# Spartan6-IO23.net
KiCad netlist of a schematic drawn in Altium Designer
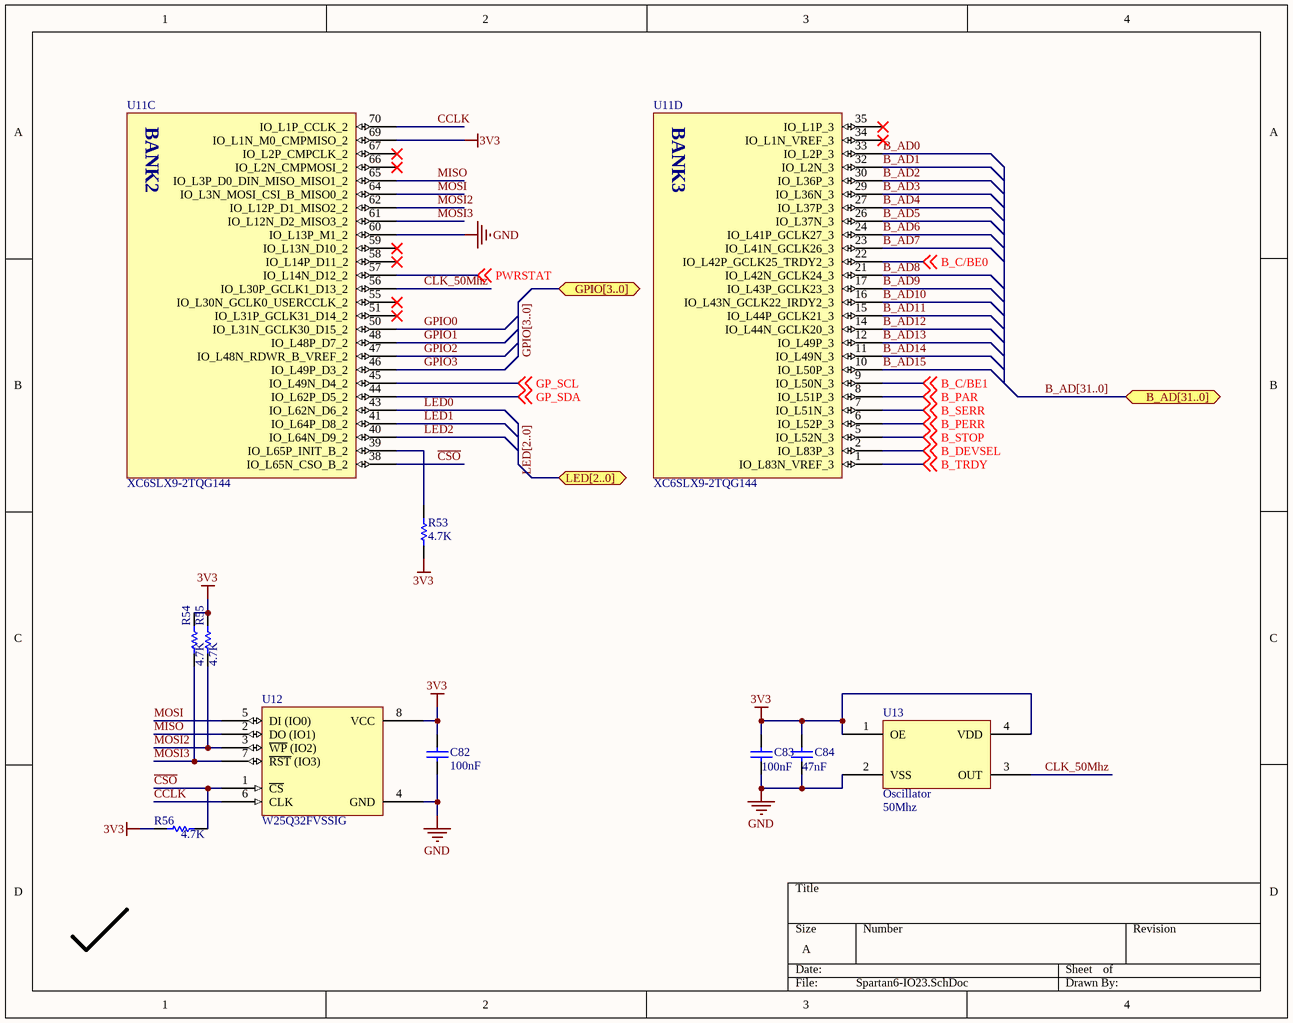
[diagram p0: Spartan6-IO23.SchDoc]

(export (version "E")
  (design (tool "Eeschema 10.0.6"))
  (components
    (comp (ref "C82")
      (value "100nF")
      (footprint "0603PKG")
      (description "Capacitor (Semiconductor SIM Model)")
      (fields (field (name "Comment") "Cap Semi") (field (name "PUBLISHER") "Altium Limited"))
      (libsource (lib "Miscellaneous Devices") (part "Cap Semi"))
    )
    (comp (ref "C83")
      (value "100nF")
      (footprint "0603PKG")
      (description "Capacitor")
      (fields (field (name "Comment") "Cap") (field (name "PUBLISHER") "Altium Limited"))
      (libsource (lib "Miscellaneous Devices") (part "Cap"))
    )
    (comp (ref "C84")
      (value "47nF")
      (footprint "0603PKG")
      (description "Capacitor")
      (fields (field (name "Comment") "Cap") (field (name "PUBLISHER") "Altium Limited"))
      (libsource (lib "Miscellaneous Devices") (part "Cap"))
    )
    (comp (ref "R53")
      (value "4.7K")
      (footprint "0603PKG")
      (description "Resistor")
      (fields (field (name "Comment") "Res1") (field (name "PUBLISHER") "Altium Limited"))
      (libsource (lib "Miscellaneous Devices") (part "Res1"))
    )
    (comp (ref "R54")
      (value "4.7K")
      (footprint "0603PKG")
      (description "Resistor")
      (fields (field (name "Comment") "Res1") (field (name "PUBLISHER") "Altium Limited"))
      (libsource (lib "Miscellaneous Devices") (part "Res1"))
    )
    (comp (ref "R55")
      (value "4.7K")
      (footprint "0603PKG")
      (description "Resistor")
      (fields (field (name "Comment") "Res1") (field (name "PUBLISHER") "Altium Limited"))
      (libsource (lib "Miscellaneous Devices") (part "Res1"))
    )
    (comp (ref "R56")
      (value "4.7K")
      (footprint "0603PKG")
      (description "Resistor")
      (fields (field (name "Comment") "Res1") (field (name "PUBLISHER") "Altium Limited"))
      (libsource (lib "Miscellaneous Devices") (part "Res1"))
    )
    (comp (ref "U11")
      (value "XC6SLX9-2TQG144")
      (footprint "TQG144")
      (description "Xilinx Spartan6 LX9")
      (libsource (lib "Connector_IntLib") (part "XC6SLX9-2TQG144C"))
    )
    (comp (ref "U12")
      (value "W25Q32FVSSIG")
      (footprint "SSOP8")
      (libsource (lib "Connector_IntLib") (part "W25Q32FVSSIG"))
    )
    (comp (ref "U13")
      (value "Oscillator")
      (footprint "Crystal5x7")
      (fields (field (name "FREQ") "50Mhz"))
      (libsource (lib "Connector_IntLib") (part "Oscillator"))
    )
  )
  (nets
    (net (code "17") (name "/B_AD0") (class "Default")
      (node (ref "U11") (pin "33") (pinfunction "IO_L2P_3_33") (pintype "bidirectional"))
    )
    (net (code "18") (name "/B_AD1") (class "Default")
      (node (ref "U11") (pin "32") (pinfunction "IO_L2N_3_32") (pintype "bidirectional"))
    )
    (net (code "19") (name "/B_AD2") (class "Default")
      (node (ref "U11") (pin "30") (pinfunction "IO_L36P_3_30") (pintype "bidirectional"))
    )
    (net (code "20") (name "/B_AD3") (class "Default")
      (node (ref "U11") (pin "29") (pinfunction "IO_L36N_3_29") (pintype "bidirectional"))
    )
    (net (code "21") (name "/B_AD4") (class "Default")
      (node (ref "U11") (pin "27") (pinfunction "IO_L37P_3_27") (pintype "bidirectional"))
    )
    (net (code "22") (name "/B_AD5") (class "Default")
      (node (ref "U11") (pin "26") (pinfunction "IO_L37N_3_26") (pintype "bidirectional"))
    )
    (net (code "23") (name "/B_AD6") (class "Default")
      (node (ref "U11") (pin "24") (pinfunction "IO_L41P_GCLK27_3_24") (pintype "bidirectional"))
    )
    (net (code "24") (name "/B_AD7") (class "Default")
      (node (ref "U11") (pin "23") (pinfunction "IO_L41N_GCLK26_3_23") (pintype "bidirectional"))
    )
    (net (code "25") (name "/B_AD8") (class "Default")
      (node (ref "U11") (pin "21") (pinfunction "IO_L42N_GCLK24_3_21") (pintype "bidirectional"))
    )
    (net (code "26") (name "/B_AD9") (class "Default")
      (node (ref "U11") (pin "17") (pinfunction "IO_L43P_GCLK23_3_17") (pintype "bidirectional"))
    )
    (net (code "27") (name "/B_AD10") (class "Default")
      (node (ref "U11") (pin "16") (pinfunction "IO_L43N_GCLK22_IRDY2_3_16") (pintype "bidirectional"))
    )
    (net (code "28") (name "/B_AD11") (class "Default")
      (node (ref "U11") (pin "15") (pinfunction "IO_L44P_GCLK21_3_15") (pintype "bidirectional"))
    )
    (net (code "29") (name "/B_AD12") (class "Default")
      (node (ref "U11") (pin "14") (pinfunction "IO_L44N_GCLK20_3_14") (pintype "bidirectional"))
    )
    (net (code "30") (name "/B_AD13") (class "Default")
      (node (ref "U11") (pin "12") (pinfunction "IO_L49P_3_12") (pintype "bidirectional"))
    )
    (net (code "31") (name "/B_AD14") (class "Default")
      (node (ref "U11") (pin "11") (pinfunction "IO_L49N_3_11") (pintype "bidirectional"))
    )
    (net (code "32") (name "/B_AD15") (class "Default")
      (node (ref "U11") (pin "10") (pinfunction "IO_L50P_3_10") (pintype "bidirectional"))
    )
    (net (code "34") (name "/CCLK") (class "Default")
      (node (ref "U11") (pin "70") (pinfunction "IO_L1P_CCLK_2_70") (pintype "bidirectional"))
      (node (ref "U12") (pin "6") (pinfunction "CLK_6") (pintype "input"))
    )
    (net (code "35") (name "/CLK_50Mhz") (class "Default")
      (node (ref "U11") (pin "56") (pinfunction "IO_L30P_GCLK1_D13_2_56") (pintype "bidirectional"))
      (node (ref "U13") (pin "3") (pinfunction "OUT_3") (pintype "passive"))
    )
    (net (code "36") (name "/GPIO0") (class "Default")
      (node (ref "U11") (pin "50") (pinfunction "IO_L31N_GCLK30_D15_2_50") (pintype "bidirectional"))
    )
    (net (code "37") (name "/GPIO1") (class "Default")
      (node (ref "U11") (pin "48") (pinfunction "IO_L48P_D7_2_48") (pintype "bidirectional"))
    )
    (net (code "38") (name "/GPIO2") (class "Default")
      (node (ref "U11") (pin "47") (pinfunction "IO_L48N_RDWR_B_VREF_2_47") (pintype "bidirectional"))
    )
    (net (code "39") (name "/GPIO3") (class "Default")
      (node (ref "U11") (pin "46") (pinfunction "IO_L49P_D3_2_46") (pintype "bidirectional"))
    )
    (net (code "41") (name "/LED0") (class "Default")
      (node (ref "U11") (pin "43") (pinfunction "IO_L62N_D6_2_43") (pintype "bidirectional"))
    )
    (net (code "42") (name "/LED1") (class "Default")
      (node (ref "U11") (pin "41") (pinfunction "IO_L64P_D8_2_41") (pintype "bidirectional"))
    )
    (net (code "43") (name "/LED2") (class "Default")
      (node (ref "U11") (pin "40") (pinfunction "IO_L64N_D9_2_40") (pintype "bidirectional"))
    )
    (net (code "45") (name "/MISO") (class "Default")
      (node (ref "U11") (pin "65") (pinfunction "IO_L3P_D0_DIN_MISO_MISO1_2_65") (pintype "bidirectional"))
      (node (ref "U12") (pin "2") (pinfunction "DO_(IO1)_2") (pintype "bidirectional"))
    )
    (net (code "46") (name "/MOSI") (class "Default")
      (node (ref "U11") (pin "64") (pinfunction "IO_L3N_MOSI_CSI_B_MISO0_2_64") (pintype "bidirectional"))
      (node (ref "U12") (pin "5") (pinfunction "DI_(IO0)_5") (pintype "bidirectional"))
    )
    (net (code "47") (name "/MOSI2") (class "Default")
      (node (ref "R55") (pin "1") (pinfunction "1_1") (pintype "passive"))
      (node (ref "U11") (pin "62") (pinfunction "IO_L12P_D1_MISO2_2_62") (pintype "bidirectional"))
      (node (ref "U12") (pin "3") (pinfunction "~{WP}_(IO2)_3") (pintype "bidirectional"))
    )
    (net (code "48") (name "/MOSI3") (class "Default")
      (node (ref "R54") (pin "1") (pinfunction "1_1") (pintype "passive"))
      (node (ref "U11") (pin "61") (pinfunction "IO_L12N_D2_MISO3_2_61") (pintype "bidirectional"))
      (node (ref "U12") (pin "7") (pinfunction "~{RST}_(IO3)_7") (pintype "bidirectional"))
    )
    (net (code "49") (name "/~{CSO}") (class "Default")
      (node (ref "R56") (pin "2") (pinfunction "2_2") (pintype "passive"))
      (node (ref "U11") (pin "38") (pinfunction "IO_L65N_CSO_B_2_38") (pintype "bidirectional"))
      (node (ref "U12") (pin "1") (pinfunction "~{CS}_1") (pintype "input"))
    )
    (net (code "50") (name "3V3") (class "Default")
      (node (ref "C82") (pin "1") (pinfunction "1_1") (pintype "passive"))
      (node (ref "C83") (pin "2") (pinfunction "2_2") (pintype "passive"))
      (node (ref "C84") (pin "2") (pinfunction "2_2") (pintype "passive"))
      (node (ref "R53") (pin "2") (pinfunction "2_2") (pintype "passive"))
      (node (ref "R54") (pin "2") (pinfunction "2_2") (pintype "passive"))
      (node (ref "R55") (pin "2") (pinfunction "2_2") (pintype "passive"))
      (node (ref "R56") (pin "1") (pinfunction "1_1") (pintype "passive"))
      (node (ref "U11") (pin "69") (pinfunction "IO_L1N_M0_CMPMISO_2_69") (pintype "bidirectional"))
      (node (ref "U12") (pin "8") (pinfunction "VCC_8") (pintype "power_in"))
      (node (ref "U13") (pin "1") (pinfunction "OE_1") (pintype "passive"))
      (node (ref "U13") (pin "4") (pinfunction "VDD_4") (pintype "passive"))
    )
    (net (code "51") (name "B_C{slash}BE0") (class "Default")
      (node (ref "U11") (pin "22") (pinfunction "IO_L42P_GCLK25_TRDY2_3_22") (pintype "bidirectional"))
    )
    (net (code "52") (name "B_C{slash}BE1") (class "Default")
      (node (ref "U11") (pin "9") (pinfunction "IO_L50N_3_9") (pintype "bidirectional"))
    )
    (net (code "53") (name "B_DEVSEL") (class "Default")
      (node (ref "U11") (pin "2") (pinfunction "IO_L83P_3_2") (pintype "bidirectional"))
    )
    (net (code "54") (name "B_PAR") (class "Default")
      (node (ref "U11") (pin "8") (pinfunction "IO_L51P_3_8") (pintype "bidirectional"))
    )
    (net (code "55") (name "B_PERR") (class "Default")
      (node (ref "U11") (pin "6") (pinfunction "IO_L52P_3_6") (pintype "bidirectional"))
    )
    (net (code "56") (name "B_SERR") (class "Default")
      (node (ref "U11") (pin "7") (pinfunction "IO_L51N_3_7") (pintype "bidirectional"))
    )
    (net (code "57") (name "B_STOP") (class "Default")
      (node (ref "U11") (pin "5") (pinfunction "IO_L52N_3_5") (pintype "bidirectional"))
    )
    (net (code "58") (name "B_TRDY") (class "Default")
      (node (ref "U11") (pin "1") (pinfunction "IO_L83N_VREF_3_1") (pintype "bidirectional"))
    )
    (net (code "59") (name "GND") (class "Default")
      (node (ref "C82") (pin "2") (pinfunction "2_2") (pintype "passive"))
      (node (ref "C83") (pin "1") (pinfunction "1_1") (pintype "passive"))
      (node (ref "C84") (pin "1") (pinfunction "1_1") (pintype "passive"))
      (node (ref "U11") (pin "60") (pinfunction "IO_L13P_M1_2_60") (pintype "bidirectional"))
      (node (ref "U12") (pin "4") (pinfunction "GND_4") (pintype "power_in"))
      (node (ref "U13") (pin "2") (pinfunction "VSS_2") (pintype "passive"))
    )
    (net (code "60") (name "GP_SCL") (class "Default")
      (node (ref "U11") (pin "45") (pinfunction "IO_L49N_D4_2_45") (pintype "bidirectional"))
    )
    (net (code "61") (name "GP_SDA") (class "Default")
      (node (ref "U11") (pin "44") (pinfunction "IO_L62P_D5_2_44") (pintype "bidirectional"))
    )
    (net (code "62") (name "Net-(U11C-IO_L65P_INIT_B_2)") (class "Default")
      (node (ref "R53") (pin "1") (pinfunction "1_1") (pintype "passive"))
      (node (ref "U11") (pin "39") (pinfunction "IO_L65P_INIT_B_2_39") (pintype "bidirectional"))
    )
    (net (code "63") (name "PWRSTAT") (class "Default")
      (node (ref "U11") (pin "57") (pinfunction "IO_L14N_D12_2_57") (pintype "bidirectional"))
    )
    (net (code "64") (name "unconnected-(U11C-IO_L2N_CMPMOSI_2-Pad66)") (class "Default")
      (node (ref "U11") (pin "66") (pinfunction "IO_L2N_CMPMOSI_2_66") (pintype "bidirectional+no_connect"))
    )
    (net (code "65") (name "unconnected-(U11C-IO_L2P_CMPCLK_2-Pad67)") (class "Default")
      (node (ref "U11") (pin "67") (pinfunction "IO_L2P_CMPCLK_2_67") (pintype "bidirectional+no_connect"))
    )
    (net (code "66") (name "unconnected-(U11C-IO_L13N_D10_2-Pad59)") (class "Default")
      (node (ref "U11") (pin "59") (pinfunction "IO_L13N_D10_2_59") (pintype "bidirectional+no_connect"))
    )
    (net (code "67") (name "unconnected-(U11C-IO_L14P_D11_2-Pad58)") (class "Default")
      (node (ref "U11") (pin "58") (pinfunction "IO_L14P_D11_2_58") (pintype "bidirectional+no_connect"))
    )
    (net (code "68") (name "unconnected-(U11C-IO_L30N_GCLK0_USERCCLK_2-Pad55)") (class "Default")
      (node (ref "U11") (pin "55") (pinfunction "IO_L30N_GCLK0_USERCCLK_2_55") (pintype "bidirectional+no_connect"))
    )
    (net (code "69") (name "unconnected-(U11C-IO_L31P_GCLK31_D14_2-Pad51)") (class "Default")
      (node (ref "U11") (pin "51") (pinfunction "IO_L31P_GCLK31_D14_2_51") (pintype "bidirectional+no_connect"))
    )
    (net (code "70") (name "unconnected-(U11D-IO_L1N_VREF_3-Pad34)") (class "Default")
      (node (ref "U11") (pin "34") (pinfunction "IO_L1N_VREF_3_34") (pintype "bidirectional+no_connect"))
    )
    (net (code "71") (name "unconnected-(U11D-IO_L1P_3-Pad35)") (class "Default")
      (node (ref "U11") (pin "35") (pinfunction "IO_L1P_3_35") (pintype "bidirectional+no_connect"))
    )
  )
)
